# LED-Chaser.net
KiCad netlist of a schematic drawn in Altium Designer
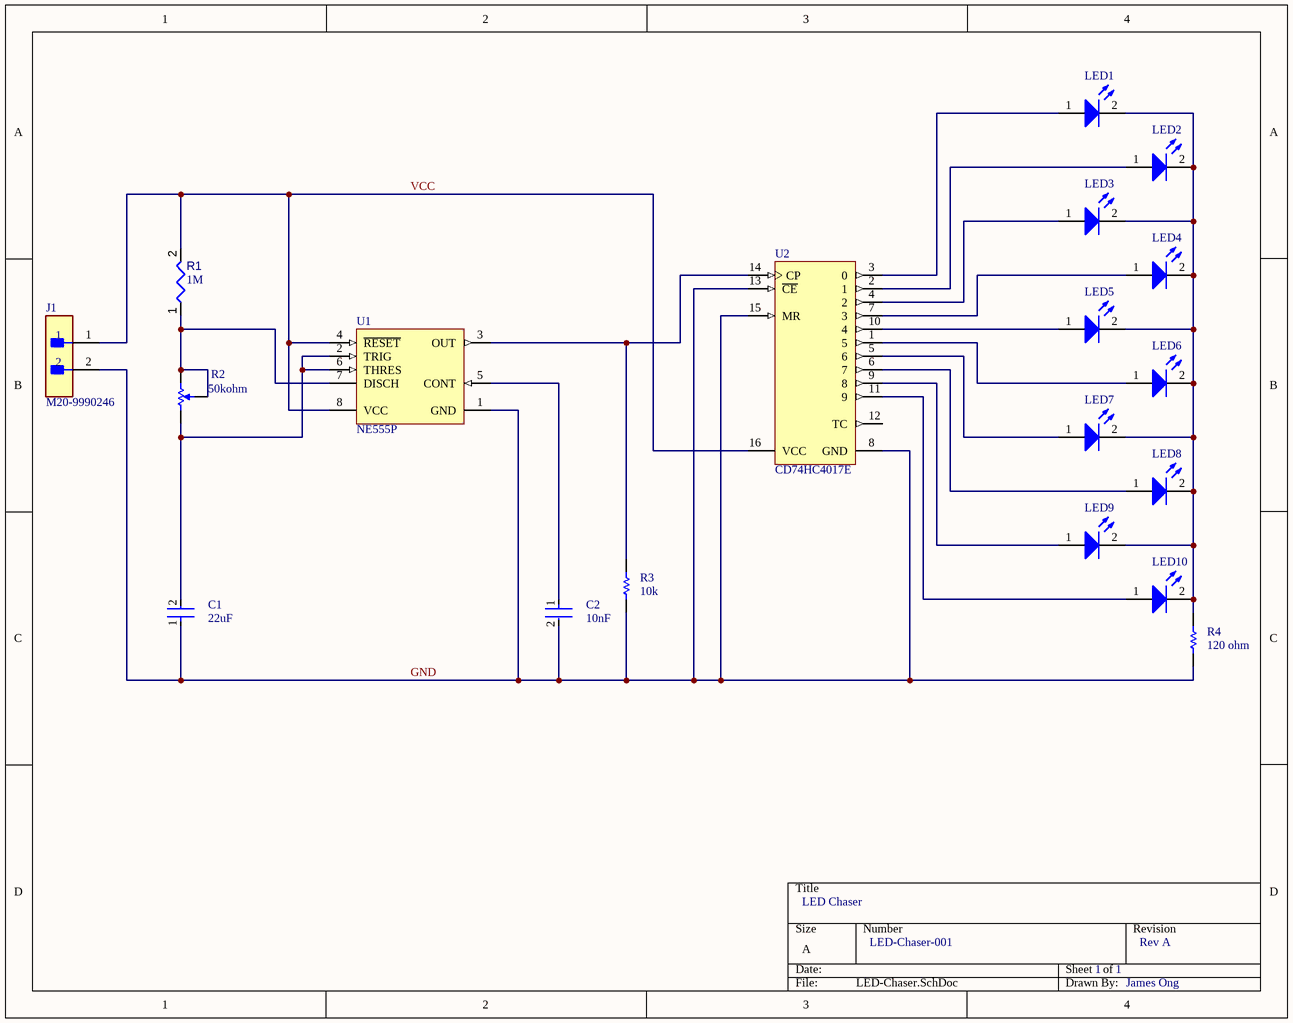
[diagram p0: LED-Chaser.SchDoc]

(export (version "E")
  (design (tool "Eeschema 10.0.6"))
  (components
    (comp (ref "C1")
      (value "RCER71E226MWM1H03A")
      (footprint "FP-RCEWM1-MFG")
      (description "CAP CER 22UF 25V X7R RADIAL")
      (fields (field (name "CAPACITANCE") "22uF") (field (name "TOLERANCE") "20%"))
      (libsource (lib "Altium Content Vault") (part "02cd4be3c70576c341d710602a673aa"))
    )
    (comp (ref "C2")
      (value "RCER71H103K0K1H03B")
      (footprint "FP-RCE0K1-MFG")
      (description "Cap Ceramic 10nF 50V X7R ±10% Radial 5mm +125°C Automotive Bulk")
      (fields (field (name "CAPACITANCE") "10nF") (field (name "TOLERANCE") "10%"))
      (libsource (lib "Altium Content Vault") (part "b4654b650e69147ec39a6b967a45e02"))
    )
    (comp (ref "J1")
      (value "M20-9990246")
      (footprint "FP-M20-9990246-MFG")
      (description "CONN HEADER VERT 2POS 2.54MM")
      (fields
        (field (name "OCTOPART") "https://octopart.com/m20-9990246-harwin-2590635")
        (field (name "MANUFACTURER") "Harwin")
      )
      (libsource (lib "Altium Content Vault") (part "3bc925449376181038e59eaffc5286c"))
    )
    (comp (ref "LED1")
      (value "151051BS04000")
      (footprint "WL-TMRC_D5.9H8.7")
      (libsource (lib "Altium Content Vault") (part "LED_Blue_1A-2K"))
    )
    (comp (ref "LED2")
      (value "151051BS04000")
      (footprint "WL-TMRC_D5.9H8.7")
      (libsource (lib "Altium Content Vault") (part "LED_Blue_1A-2K"))
    )
    (comp (ref "LED3")
      (value "151051BS04000")
      (footprint "WL-TMRC_D5.9H8.7")
      (libsource (lib "Altium Content Vault") (part "LED_Blue_1A-2K"))
    )
    (comp (ref "LED4")
      (value "151051BS04000")
      (footprint "WL-TMRC_D5.9H8.7")
      (libsource (lib "Altium Content Vault") (part "LED_Blue_1A-2K"))
    )
    (comp (ref "LED5")
      (value "151051BS04000")
      (footprint "WL-TMRC_D5.9H8.7")
      (libsource (lib "Altium Content Vault") (part "LED_Blue_1A-2K"))
    )
    (comp (ref "LED6")
      (value "151051BS04000")
      (footprint "WL-TMRC_D5.9H8.7")
      (libsource (lib "Altium Content Vault") (part "LED_Blue_1A-2K"))
    )
    (comp (ref "LED7")
      (value "151051BS04000")
      (footprint "WL-TMRC_D5.9H8.7")
      (libsource (lib "Altium Content Vault") (part "LED_Blue_1A-2K"))
    )
    (comp (ref "LED8")
      (value "151051BS04000")
      (footprint "WL-TMRC_D5.9H8.7")
      (libsource (lib "Altium Content Vault") (part "LED_Blue_1A-2K"))
    )
    (comp (ref "LED9")
      (value "151051BS04000")
      (footprint "WL-TMRC_D5.9H8.7")
      (libsource (lib "Altium Content Vault") (part "LED_Blue_1A-2K"))
    )
    (comp (ref "LED10")
      (value "151051BS04000")
      (footprint "WL-TMRC_D5.9H8.7")
      (libsource (lib "Altium Content Vault") (part "LED_Blue_1A-2K"))
    )
    (comp (ref "R1")
      (value "1M")
      (footprint "RESA60-630X240")
      (description "Axial Resistor, 1 MOhm, +/- 1%, 250 mW, -55 to 155 degC, 2-Pin THD, RoHS, Bulk")
      (fields (field (name "MANUFACTURER") "Yageo") (field (name "TOLERANCE") "1%"))
      (libsource (lib "James Ong PCB Design") (part "RES-2"))
    )
    (comp (ref "R2")
      (value "3313J-1-503E")
      (footprint "BOUR-3313J-1_V")
      (fields (field (name "MANUFACTURER") "Bourns") (field (name "TRACK RESISTANCE") "50kohm"))
      (libsource (lib "Altium Content Vault") (part "RES-ADJ-3_A"))
    )
    (comp (ref "R3")
      (value "OD103JE")
      (footprint "OMTE-RES7X2.5-2")
      (fields
        (field (name "RESISTANCE (OHMS)") "10k")
        (field (name "TOLERANCE") "±5%")
        (field (name "MANUFACTURER") "Ohmite")
      )
      (libsource (lib "Altium Content Vault") (part "RES-2"))
    )
    (comp (ref "R4")
      (value "OD103JE")
      (footprint "OMTE-RES7X2.5-2")
      (fields
        (field (name "RESISTANCE (OHMS)") "120 ohm")
        (field (name "TOLERANCE") "±5%")
        (field (name "MANUFACTURER") "Ohmite")
      )
      (libsource (lib "Altium Content Vault") (part "RES-2"))
    )
    (comp (ref "U1")
      (value "NE555P")
      (footprint "P0008A")
      (description "Precision Timer, 4.5 to 16 V, 0 to 70 degC, 8-Pin DIP, Pb-Free, Tube")
      (fields (field (name "MANUFACTURER") "TexasInstruments"))
      (libsource (lib "Altium Content Vault") (part "TI-NE555-P8"))
    )
    (comp (ref "U2")
      (value "CD74HC4017E")
      (footprint "N0016A")
      (description "High Speed CMOS Logic Decade Counter/Divider with 10 Decoded Outputs, N0016A, TUBE")
      (fields
        (field (name "GENERIC PART NUMBER") "CD74HC4017")
        (field (name "MANUFACTURER") "Texas Instruments")
      )
      (libsource (lib "Altium Content Vault") (part "TI-CD74HC4017-16"))
    )
  )
  (nets
    (net (code "1") (name "/GND") (class "Default")
      (node (ref "C1") (pin "1") (pinfunction "1_1") (pintype "passive"))
      (node (ref "C2") (pin "2") (pinfunction "2_2") (pintype "passive"))
      (node (ref "J1") (pin "2") (pinfunction "2_2") (pintype "passive"))
      (node (ref "R3") (pin "1") (pinfunction "1_1") (pintype "passive"))
      (node (ref "R4") (pin "1") (pinfunction "1_1") (pintype "passive"))
      (node (ref "U1") (pin "1") (pinfunction "GND_1") (pintype "power_in"))
      (node (ref "U2") (pin "13") (pinfunction "~{CE}_13") (pintype "input"))
      (node (ref "U2") (pin "15") (pinfunction "MR_15") (pintype "input"))
      (node (ref "U2") (pin "8") (pinfunction "GND_8") (pintype "power_in"))
    )
    (net (code "2") (name "/VCC") (class "Default")
      (node (ref "J1") (pin "1") (pinfunction "1_1") (pintype "passive"))
      (node (ref "R1") (pin "2") (pinfunction "2_2") (pintype "passive"))
      (node (ref "U1") (pin "4") (pinfunction "~{RESET}_4") (pintype "input"))
      (node (ref "U1") (pin "8") (pinfunction "VCC_8") (pintype "power_in"))
      (node (ref "U2") (pin "16") (pinfunction "VCC_16") (pintype "power_in"))
    )
    (net (code "3") (name "Net-(LED1-A)") (class "Default")
      (node (ref "LED1") (pin "1") (pinfunction "A_1") (pintype "passive"))
      (node (ref "U2") (pin "3") (pinfunction "0_3") (pintype "output"))
    )
    (net (code "4") (name "Net-(LED1-K)") (class "Default")
      (node (ref "LED1") (pin "2") (pinfunction "K_2") (pintype "passive"))
      (node (ref "LED10") (pin "2") (pinfunction "K_2") (pintype "passive"))
      (node (ref "LED2") (pin "2") (pinfunction "K_2") (pintype "passive"))
      (node (ref "LED3") (pin "2") (pinfunction "K_2") (pintype "passive"))
      (node (ref "LED4") (pin "2") (pinfunction "K_2") (pintype "passive"))
      (node (ref "LED5") (pin "2") (pinfunction "K_2") (pintype "passive"))
      (node (ref "LED6") (pin "2") (pinfunction "K_2") (pintype "passive"))
      (node (ref "LED7") (pin "2") (pinfunction "K_2") (pintype "passive"))
      (node (ref "LED8") (pin "2") (pinfunction "K_2") (pintype "passive"))
      (node (ref "LED9") (pin "2") (pinfunction "K_2") (pintype "passive"))
      (node (ref "R4") (pin "2") (pinfunction "2_2") (pintype "passive"))
    )
    (net (code "5") (name "Net-(LED2-A)") (class "Default")
      (node (ref "LED2") (pin "1") (pinfunction "A_1") (pintype "passive"))
      (node (ref "U2") (pin "2") (pinfunction "1_2") (pintype "output"))
    )
    (net (code "6") (name "Net-(LED3-A)") (class "Default")
      (node (ref "LED3") (pin "1") (pinfunction "A_1") (pintype "passive"))
      (node (ref "U2") (pin "4") (pinfunction "2_4") (pintype "output"))
    )
    (net (code "7") (name "Net-(LED4-A)") (class "Default")
      (node (ref "LED4") (pin "1") (pinfunction "A_1") (pintype "passive"))
      (node (ref "U2") (pin "7") (pinfunction "3_7") (pintype "output"))
    )
    (net (code "8") (name "Net-(LED5-A)") (class "Default")
      (node (ref "LED5") (pin "1") (pinfunction "A_1") (pintype "passive"))
      (node (ref "U2") (pin "10") (pinfunction "4_10") (pintype "output"))
    )
    (net (code "9") (name "Net-(LED6-A)") (class "Default")
      (node (ref "LED6") (pin "1") (pinfunction "A_1") (pintype "passive"))
      (node (ref "U2") (pin "1") (pinfunction "5_1") (pintype "output"))
    )
    (net (code "10") (name "Net-(LED7-A)") (class "Default")
      (node (ref "LED7") (pin "1") (pinfunction "A_1") (pintype "passive"))
      (node (ref "U2") (pin "5") (pinfunction "6_5") (pintype "output"))
    )
    (net (code "11") (name "Net-(LED8-A)") (class "Default")
      (node (ref "LED8") (pin "1") (pinfunction "A_1") (pintype "passive"))
      (node (ref "U2") (pin "6") (pinfunction "7_6") (pintype "output"))
    )
    (net (code "12") (name "Net-(LED9-A)") (class "Default")
      (node (ref "LED9") (pin "1") (pinfunction "A_1") (pintype "passive"))
      (node (ref "U2") (pin "9") (pinfunction "8_9") (pintype "output"))
    )
    (net (code "13") (name "Net-(LED10-A)") (class "Default")
      (node (ref "LED10") (pin "1") (pinfunction "A_1") (pintype "passive"))
      (node (ref "U2") (pin "11") (pinfunction "9_11") (pintype "output"))
    )
    (net (code "14") (name "Net-(U1-CONT)") (class "Default")
      (node (ref "C2") (pin "1") (pinfunction "1_1") (pintype "passive"))
      (node (ref "U1") (pin "5") (pinfunction "CONT_5") (pintype "input"))
    )
    (net (code "15") (name "Net-(U1-DISCH)") (class "Default")
      (node (ref "R1") (pin "1") (pinfunction "1_1") (pintype "passive"))
      (node (ref "R2") (pin "2") (pinfunction "2_2") (pintype "passive"))
      (node (ref "R2") (pin "3") (pinfunction "3_3") (pintype "passive"))
      (node (ref "U1") (pin "7") (pinfunction "DISCH_7") (pintype "open_collector"))
    )
    (net (code "16") (name "Net-(U1-OUT)") (class "Default")
      (node (ref "R3") (pin "2") (pinfunction "2_2") (pintype "passive"))
      (node (ref "U1") (pin "3") (pinfunction "OUT_3") (pintype "output"))
      (node (ref "U2") (pin "14") (pinfunction "CP_14") (pintype "input"))
    )
    (net (code "17") (name "Net-(U1-THRES)") (class "Default")
      (node (ref "C1") (pin "2") (pinfunction "2_2") (pintype "passive"))
      (node (ref "R2") (pin "1") (pinfunction "1_1") (pintype "passive"))
      (node (ref "U1") (pin "2") (pinfunction "TRIG_2") (pintype "input"))
      (node (ref "U1") (pin "6") (pinfunction "THRES_6") (pintype "input"))
    )
    (net (code "18") (name "unconnected-(U2-TC-Pad12)") (class "Default")
      (node (ref "U2") (pin "12") (pinfunction "TC_12") (pintype "output"))
    )
  )
)
